# CurrentMeter.net
KiCad netlist of a schematic drawn in Altium Designer
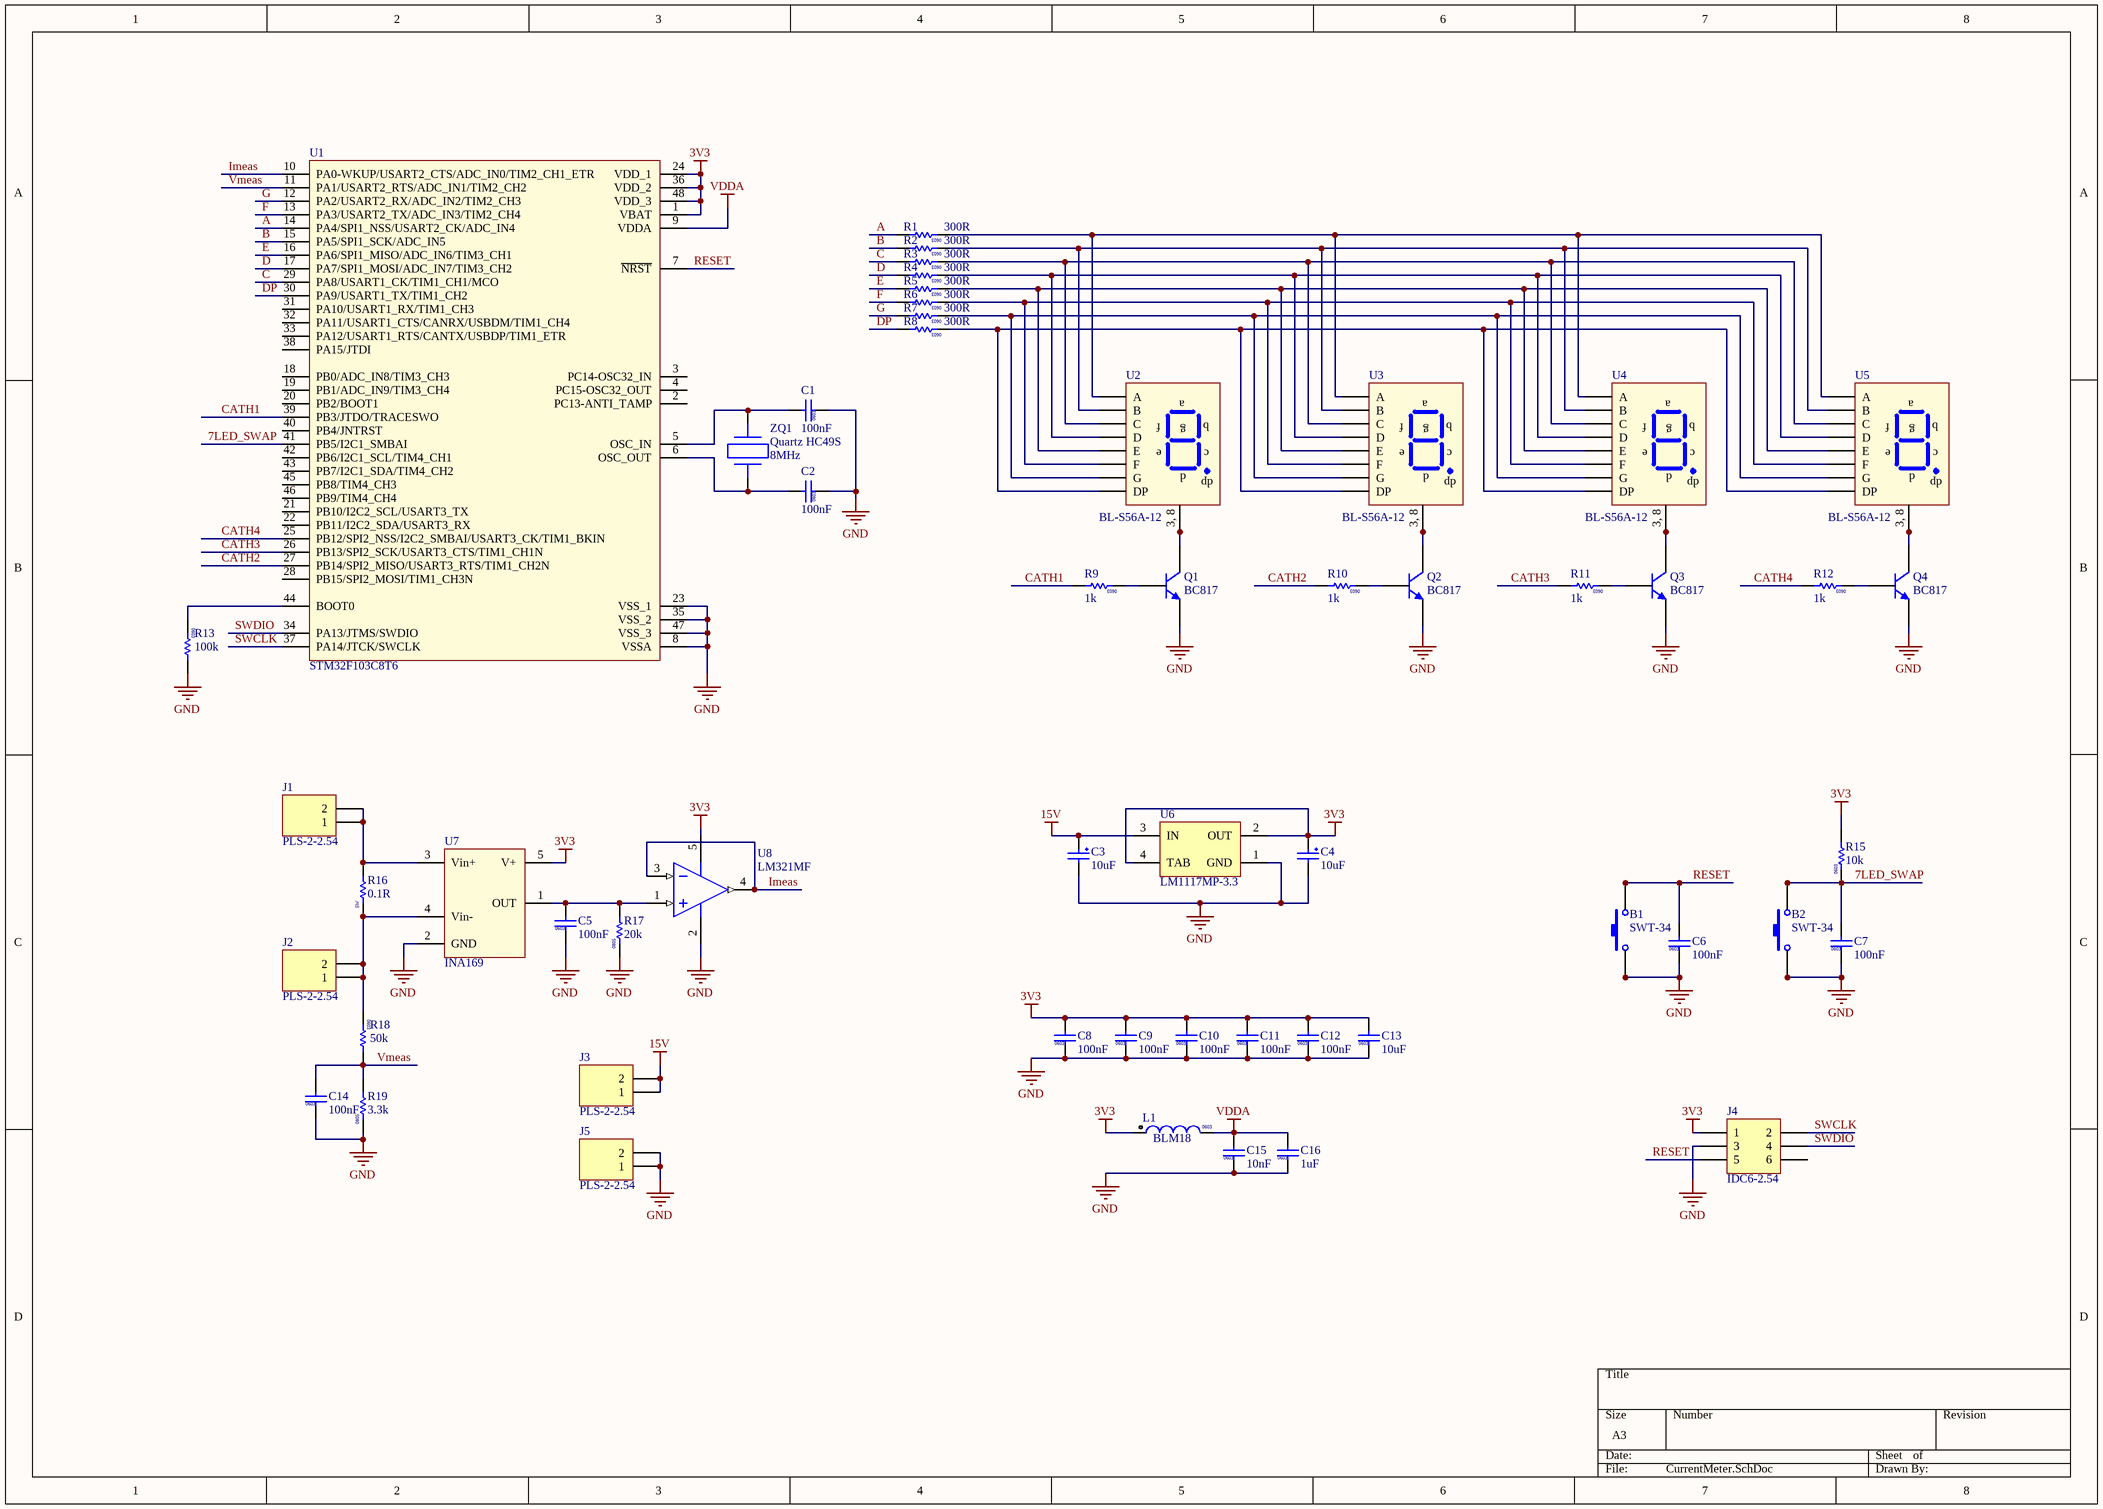
[diagram p0: CurrentMeter.SchDoc]

(export (version "E")
  (design (tool "Eeschema 10.0.6"))
  (components
    (comp (ref "B1")
      (value "SWT-34")
      (footprint "SWT-34")
      (description "KLS7-TS6604-7.0-180-T, SMD Button h=7mm")
      (libsource (lib "Connectors_dif") (part "SWT-34"))
    )
    (comp (ref "B2")
      (value "SWT-34")
      (footprint "SWT-34")
      (description "KLS7-TS6604-7.0-180-T, SMD Button h=7mm")
      (libsource (lib "Connectors_dif") (part "SWT-34"))
    )
    (comp (ref "C1")
      (value "100nF")
      (footprint "CAPC1608-0603N")
      (description "Capacitor 0603")
      (fields (field (name "Comment") "CAPC_0603"))
      (libsource (lib "Passive") (part "CAPC_0603"))
    )
    (comp (ref "C2")
      (value "100nF")
      (footprint "CAPC1608-0603N")
      (description "Capacitor 0603")
      (fields (field (name "Comment") "CAPC_0603"))
      (libsource (lib "Passive") (part "CAPC_0603"))
    )
    (comp (ref "C3")
      (value "10uF")
      (footprint "TCAPC_A")
      (description "Capacitor tantalum SMD type A")
      (fields (field (name "Comment") "TCAPC_A"))
      (libsource (lib "Passive") (part "TCAPC_A"))
    )
    (comp (ref "C4")
      (value "10uF")
      (footprint "TCAPC_A")
      (description "Capacitor tantalum SMD type A")
      (fields (field (name "Comment") "TCAPC_A"))
      (libsource (lib "Passive") (part "TCAPC_A"))
    )
    (comp (ref "C5")
      (value "100nF")
      (footprint "CAPC1608-0603N")
      (description "Capacitor 0603")
      (fields (field (name "Comment") "CAPC_0603"))
      (libsource (lib "Passive") (part "CAPC_0603"))
    )
    (comp (ref "C6")
      (value "100nF")
      (footprint "CAPC1608-0603N")
      (description "Capacitor 0603")
      (fields (field (name "Comment") "CAPC_0603"))
      (libsource (lib "Passive") (part "CAPC_0603"))
    )
    (comp (ref "C7")
      (value "100nF")
      (footprint "CAPC1608-0603N")
      (description "Capacitor 0603")
      (fields (field (name "Comment") "CAPC_0603"))
      (libsource (lib "Passive") (part "CAPC_0603"))
    )
    (comp (ref "C8")
      (value "100nF")
      (footprint "CAPC1608-0603N")
      (description "Capacitor 0603")
      (fields (field (name "Comment") "CAPC_0603"))
      (libsource (lib "Passive") (part "CAPC_0603"))
    )
    (comp (ref "C9")
      (value "100nF")
      (footprint "CAPC1608-0603N")
      (description "Capacitor 0603")
      (fields (field (name "Comment") "CAPC_0603"))
      (libsource (lib "Passive") (part "CAPC_0603"))
    )
    (comp (ref "C10")
      (value "100nF")
      (footprint "CAPC1608-0603N")
      (description "Capacitor 0603")
      (fields (field (name "Comment") "CAPC_0603"))
      (libsource (lib "Passive") (part "CAPC_0603"))
    )
    (comp (ref "C11")
      (value "100nF")
      (footprint "CAPC1608-0603N")
      (description "Capacitor 0603")
      (fields (field (name "Comment") "CAPC_0603"))
      (libsource (lib "Passive") (part "CAPC_0603"))
    )
    (comp (ref "C12")
      (value "100nF")
      (footprint "CAPC1608-0603N")
      (description "Capacitor 0603")
      (fields (field (name "Comment") "CAPC_0603"))
      (libsource (lib "Passive") (part "CAPC_0603"))
    )
    (comp (ref "C13")
      (value "10uF")
      (footprint "CAPC1608-0603N")
      (description "Capacitor 0603")
      (fields (field (name "Comment") "CAPC_0603"))
      (libsource (lib "Passive") (part "CAPC_0603"))
    )
    (comp (ref "C14")
      (value "100nF")
      (footprint "CAPC1608-0603N")
      (description "Capacitor 0603")
      (fields (field (name "Comment") "CAPC_0603"))
      (libsource (lib "Passive") (part "CAPC_0603"))
    )
    (comp (ref "C15")
      (value "10nF")
      (footprint "CAPC1608-0603N")
      (description "Capacitor 0603")
      (fields (field (name "Comment") "CAPC_0603"))
      (libsource (lib "Passive") (part "CAPC_0603"))
    )
    (comp (ref "C16")
      (value "1uF")
      (footprint "CAPC1608-0603N")
      (description "Capacitor 0603")
      (fields (field (name "Comment") "CAPC_0603"))
      (libsource (lib "Passive") (part "CAPC_0603"))
    )
    (comp (ref "J1")
      (value "PLS-2-2.54")
      (footprint "PLS-2-2.54")
      (fields (field (name "PUBLISHER") "Altium Limited"))
      (libsource (lib "Connectors_dif") (part "PLS-2-2.54"))
    )
    (comp (ref "J2")
      (value "PLS-2-2.54")
      (footprint "PLS-2-2.54")
      (fields (field (name "PUBLISHER") "Altium Limited"))
      (libsource (lib "Connectors_dif") (part "PLS-2-2.54"))
    )
    (comp (ref "J3")
      (value "PLS-2-2.54")
      (footprint "PLS-2-2.54")
      (fields (field (name "PUBLISHER") "Altium Limited"))
      (libsource (lib "Connectors_dif") (part "PLS-2-2.54"))
    )
    (comp (ref "J4")
      (value "IDC6-2.54")
      (footprint "IDC6-2.54")
      (description "IDC6 2.54 mm pitch Straight, plastic Box")
      (libsource (lib "Connectors_dif") (part "IDC6-2.54"))
    )
    (comp (ref "J5")
      (value "PLS-2-2.54")
      (footprint "PLS-2-2.54")
      (fields (field (name "PUBLISHER") "Altium Limited"))
      (libsource (lib "Connectors_dif") (part "PLS-2-2.54"))
    )
    (comp (ref "L1")
      (value "BLM18")
      (footprint "INDC1608AN")
      (description "Chip Inductor, Body Body 1.6x0.8mm")
      (fields (field (name "Comment") "INDC-0603"))
      (libsource (lib "Passive") (part "INDC-0603"))
    )
    (comp (ref "Q1")
      (value "BC817")
      (footprint "SOT23-3N")
      (description "BC817 NPN Transistor")
      (libsource (lib "Discrete") (part "BC817"))
    )
    (comp (ref "Q2")
      (value "BC817")
      (footprint "SOT23-3N")
      (description "BC817 NPN Transistor")
      (libsource (lib "Discrete") (part "BC817"))
    )
    (comp (ref "Q3")
      (value "BC817")
      (footprint "SOT23-3N")
      (description "BC817 NPN Transistor")
      (libsource (lib "Discrete") (part "BC817"))
    )
    (comp (ref "Q4")
      (value "BC817")
      (footprint "SOT23-3N")
      (description "BC817 NPN Transistor")
      (libsource (lib "Discrete") (part "BC817"))
    )
    (comp (ref "R1")
      (value "300R")
      (footprint "RESC1608-0603N")
      (description "Resistor 0603")
      (fields (field (name "Comment") "RESC_0603"))
      (libsource (lib "Passive") (part "RESC_0603"))
    )
    (comp (ref "R2")
      (value "300R")
      (footprint "RESC1608-0603N")
      (description "Resistor 0603")
      (fields (field (name "Comment") "RESC_0603"))
      (libsource (lib "Passive") (part "RESC_0603"))
    )
    (comp (ref "R3")
      (value "300R")
      (footprint "RESC1608-0603N")
      (description "Resistor 0603")
      (fields (field (name "Comment") "RESC_0603"))
      (libsource (lib "Passive") (part "RESC_0603"))
    )
    (comp (ref "R4")
      (value "300R")
      (footprint "RESC1608-0603N")
      (description "Resistor 0603")
      (fields (field (name "Comment") "RESC_0603"))
      (libsource (lib "Passive") (part "RESC_0603"))
    )
    (comp (ref "R5")
      (value "300R")
      (footprint "RESC1608-0603N")
      (description "Resistor 0603")
      (fields (field (name "Comment") "RESC_0603"))
      (libsource (lib "Passive") (part "RESC_0603"))
    )
    (comp (ref "R6")
      (value "300R")
      (footprint "RESC1608-0603N")
      (description "Resistor 0603")
      (fields (field (name "Comment") "RESC_0603"))
      (libsource (lib "Passive") (part "RESC_0603"))
    )
    (comp (ref "R7")
      (value "300R")
      (footprint "RESC1608-0603N")
      (description "Resistor 0603")
      (fields (field (name "Comment") "RESC_0603"))
      (libsource (lib "Passive") (part "RESC_0603"))
    )
    (comp (ref "R8")
      (value "300R")
      (footprint "RESC1608-0603N")
      (description "Resistor 0603")
      (fields (field (name "Comment") "RESC_0603"))
      (libsource (lib "Passive") (part "RESC_0603"))
    )
    (comp (ref "R9")
      (value "1k")
      (footprint "RESC1608-0603N")
      (description "Resistor 0603")
      (fields (field (name "Comment") "RESC_0603"))
      (libsource (lib "Passive") (part "RESC_0603"))
    )
    (comp (ref "R10")
      (value "1k")
      (footprint "RESC1608-0603N")
      (description "Resistor 0603")
      (fields (field (name "Comment") "RESC_0603"))
      (libsource (lib "Passive") (part "RESC_0603"))
    )
    (comp (ref "R11")
      (value "1k")
      (footprint "RESC1608-0603N")
      (description "Resistor 0603")
      (fields (field (name "Comment") "RESC_0603"))
      (libsource (lib "Passive") (part "RESC_0603"))
    )
    (comp (ref "R12")
      (value "1k")
      (footprint "RESC1608-0603N")
      (description "Resistor 0603")
      (fields (field (name "Comment") "RESC_0603"))
      (libsource (lib "Passive") (part "RESC_0603"))
    )
    (comp (ref "R13")
      (value "100k")
      (footprint "RESC1608-0603M")
      (description "Resistor 0603")
      (fields (field (name "Comment") "RESC_0603"))
      (libsource (lib "Passive") (part "RESC_0603"))
    )
    (comp (ref "R15")
      (value "10k")
      (footprint "RESC1608-0603N")
      (description "Resistor 0603")
      (fields (field (name "Comment") "RESC_0603"))
      (libsource (lib "Passive") (part "RESC_0603"))
    )
    (comp (ref "R16")
      (value "0.1R")
      (footprint "RES5W")
      (description "Resistor 5W")
      (fields (field (name "Comment") "RES_5W"))
      (libsource (lib "Passive") (part "RES_5W"))
    )
    (comp (ref "R17")
      (value "20k")
      (footprint "RESC2012-0805N")
      (description "Resistor 0805")
      (fields (field (name "Comment") "RESC_0805"))
      (libsource (lib "Passive") (part "RESC_0805"))
    )
    (comp (ref "R18")
      (value "50k")
      (footprint "RESC1608-0603N")
      (description "Resistor 0603")
      (fields (field (name "Comment") "RESC_0603"))
      (libsource (lib "Passive") (part "RESC_0603"))
    )
    (comp (ref "R19")
      (value "3.3k")
      (footprint "RESC2012-0805N")
      (description "Resistor 0805")
      (fields (field (name "Comment") "RESC_0805"))
      (libsource (lib "Passive") (part "RESC_0805"))
    )
    (comp (ref "U1")
      (value "STM32F103C8T6")
      (footprint "QFP48_L")
      (libsource (lib "Digital_IC") (part "STM32F103C8T6"))
    )
    (comp (ref "U2")
      (value "BL-S56A-12")
      (footprint "BL-S56A-12")
      (description "LED Numeric Display, 1 Digit")
      (libsource (lib "Discrete") (part "BL-S56A-12"))
    )
    (comp (ref "U3")
      (value "BL-S56A-12")
      (footprint "BL-S56A-12")
      (description "LED Numeric Display, 1 Digit")
      (libsource (lib "Discrete") (part "BL-S56A-12"))
    )
    (comp (ref "U4")
      (value "BL-S56A-12")
      (footprint "BL-S56A-12")
      (description "LED Numeric Display, 1 Digit")
      (libsource (lib "Discrete") (part "BL-S56A-12"))
    )
    (comp (ref "U5")
      (value "BL-S56A-12")
      (footprint "BL-S56A-12")
      (description "LED Numeric Display, 1 Digit")
      (libsource (lib "Discrete") (part "BL-S56A-12"))
    )
    (comp (ref "U6")
      (value "LM1117MP-3.3")
      (footprint "MP04A_N")
      (description "800mA Low-Dropout Linear Regulator")
      (fields
        (field (name "MANUFACTURER") "National Semiconductor")
        (field (name "DIGIKEYPARTNUMBER") "LM1117MP-3.3CT-ND")
        (field (name "PUBLISHER") "Altium Limited")
      )
      (libsource (lib "Analog_IC") (part "LM1117MP-3.3"))
    )
    (comp (ref "U7")
      (value "INA169")
      (footprint "INA169_N")
      (description "High-side Current Shunt Monitor")
      (libsource (lib "Analog_IC") (part "INA169"))
    )
    (comp (ref "U8")
      (value "LM321MF")
      (footprint "MF05A_N")
      (description "Low Power Single Op Amp")
      (fields
        (field (name "MANUFACTURER") "National Semiconductor")
        (field (name "DIGIKEYPARTNUMBER") "LM321MFCT-ND")
        (field (name "PUBLISHER") "Altium Limited")
      )
      (libsource (lib "Analog_IC") (part "LM321MF"))
    )
    (comp (ref "ZQ1")
      (value "Quartz HC49S")
      (footprint "HC-49S")
      (fields (field (name "ALTIUM_VALUE") "8MHz"))
      (libsource (lib "Passive") (part "Quartz HC49S"))
    )
  )
  (nets
    (net (code "1") (name "/7LED_SWAP") (class "Default")
      (node (ref "B2") (pin "3") (pinfunction "3_3") (pintype "passive"))
      (node (ref "B2") (pin "4") (pinfunction "4_4") (pintype "passive"))
      (node (ref "C7") (pin "2") (pinfunction "2_2") (pintype "passive"))
      (node (ref "R15") (pin "1") (pinfunction "1_1") (pintype "passive"))
      (node (ref "U1") (pin "41") (pinfunction "PB5/I2C1_SMBAI_41") (pintype "passive"))
    )
    (net (code "2") (name "/A") (class "Default")
      (node (ref "R1") (pin "2") (pinfunction "2_2") (pintype "passive"))
      (node (ref "U1") (pin "14") (pinfunction "PA4/SPI1_NSS/USART2_CK/ADC_IN4_14") (pintype "passive"))
    )
    (net (code "3") (name "/B") (class "Default")
      (node (ref "R2") (pin "2") (pinfunction "2_2") (pintype "passive"))
      (node (ref "U1") (pin "15") (pinfunction "PA5/SPI1_SCK/ADC_IN5_15") (pintype "passive"))
    )
    (net (code "4") (name "/C") (class "Default")
      (node (ref "R3") (pin "2") (pinfunction "2_2") (pintype "passive"))
      (node (ref "U1") (pin "29") (pinfunction "PA8/USART1_CK/TIM1_CH1/MCO_29") (pintype "passive"))
    )
    (net (code "5") (name "/CATH1") (class "Default")
      (node (ref "R9") (pin "2") (pinfunction "2_2") (pintype "passive"))
      (node (ref "U1") (pin "39") (pinfunction "PB3/JTDO/TRACESWO_39") (pintype "passive"))
    )
    (net (code "6") (name "/CATH2") (class "Default")
      (node (ref "R10") (pin "2") (pinfunction "2_2") (pintype "passive"))
      (node (ref "U1") (pin "27") (pinfunction "PB14/SPI2_MISO/USART3_RTS/TIM1_CH2N_27") (pintype "passive"))
    )
    (net (code "7") (name "/CATH3") (class "Default")
      (node (ref "R11") (pin "2") (pinfunction "2_2") (pintype "passive"))
      (node (ref "U1") (pin "26") (pinfunction "PB13/SPI2_SCK/USART3_CTS/TIM1_CH1N_26") (pintype "passive"))
    )
    (net (code "8") (name "/CATH4") (class "Default")
      (node (ref "R12") (pin "2") (pinfunction "2_2") (pintype "passive"))
      (node (ref "U1") (pin "25") (pinfunction "PB12/SPI2_NSS/I2C2_SMBAI/USART3_CK/TIM1_BKIN_25") (pintype "passive"))
    )
    (net (code "9") (name "/D") (class "Default")
      (node (ref "R4") (pin "2") (pinfunction "2_2") (pintype "passive"))
      (node (ref "U1") (pin "17") (pinfunction "PA7/SPI1_MOSI/ADC_IN7/TIM3_CH2_17") (pintype "passive"))
    )
    (net (code "10") (name "/DP") (class "Default")
      (node (ref "R8") (pin "2") (pinfunction "2_2") (pintype "passive"))
      (node (ref "U1") (pin "30") (pinfunction "PA9/USART1_TX/TIM1_CH2_30") (pintype "passive"))
    )
    (net (code "11") (name "/E") (class "Default")
      (node (ref "R5") (pin "2") (pinfunction "2_2") (pintype "passive"))
      (node (ref "U1") (pin "16") (pinfunction "PA6/SPI1_MISO/ADC_IN6/TIM3_CH1_16") (pintype "passive"))
    )
    (net (code "12") (name "/F") (class "Default")
      (node (ref "R6") (pin "2") (pinfunction "2_2") (pintype "passive"))
      (node (ref "U1") (pin "13") (pinfunction "PA3/USART2_TX/ADC_IN3/TIM2_CH4_13") (pintype "passive"))
    )
    (net (code "13") (name "/G") (class "Default")
      (node (ref "R7") (pin "2") (pinfunction "2_2") (pintype "passive"))
      (node (ref "U1") (pin "12") (pinfunction "PA2/USART2_RX/ADC_IN2/TIM2_CH3_12") (pintype "passive"))
    )
    (net (code "14") (name "/Imeas") (class "Default")
      (node (ref "U1") (pin "10") (pinfunction "PA0-WKUP/USART2_CTS/ADC_IN0/TIM2_CH1_ETR_10") (pintype "passive"))
      (node (ref "U8") (pin "3") (pinfunction "IN-_3") (pintype "input"))
      (node (ref "U8") (pin "4") (pinfunction "OUT_4") (pintype "output"))
    )
    (net (code "15") (name "/RESET") (class "Default")
      (node (ref "B1") (pin "3") (pinfunction "3_3") (pintype "passive"))
      (node (ref "B1") (pin "4") (pinfunction "4_4") (pintype "passive"))
      (node (ref "C6") (pin "2") (pinfunction "2_2") (pintype "passive"))
      (node (ref "J4") (pin "5") (pinfunction "5_5") (pintype "passive"))
      (node (ref "U1") (pin "7") (pinfunction "~{NRST}_7") (pintype "passive"))
    )
    (net (code "16") (name "/SWCLK") (class "Default")
      (node (ref "J4") (pin "2") (pinfunction "2_2") (pintype "passive"))
      (node (ref "U1") (pin "37") (pinfunction "PA14/JTCK/SWCLK_37") (pintype "passive"))
    )
    (net (code "17") (name "/SWDIO") (class "Default")
      (node (ref "J4") (pin "4") (pinfunction "4_4") (pintype "passive"))
      (node (ref "U1") (pin "34") (pinfunction "PA13/JTMS/SWDIO_34") (pintype "passive"))
    )
    (net (code "18") (name "/Vmeas") (class "Default")
      (node (ref "C14") (pin "2") (pinfunction "2_2") (pintype "passive"))
      (node (ref "R18") (pin "2") (pinfunction "2_2") (pintype "passive"))
      (node (ref "R19") (pin "2") (pinfunction "2_2") (pintype "passive"))
      (node (ref "U1") (pin "11") (pinfunction "PA1/USART2_RTS/ADC_IN1/TIM2_CH2_11") (pintype "passive"))
    )
    (net (code "19") (name "3V3") (class "Default")
      (node (ref "C10") (pin "2") (pinfunction "2_2") (pintype "passive"))
      (node (ref "C11") (pin "2") (pinfunction "2_2") (pintype "passive"))
      (node (ref "C12") (pin "2") (pinfunction "2_2") (pintype "passive"))
      (node (ref "C13") (pin "2") (pinfunction "2_2") (pintype "passive"))
      (node (ref "C4") (pin "1") (pinfunction "1_1") (pintype "passive"))
      (node (ref "C8") (pin "2") (pinfunction "2_2") (pintype "passive"))
      (node (ref "C9") (pin "2") (pinfunction "2_2") (pintype "passive"))
      (node (ref "J4") (pin "1") (pinfunction "1_1") (pintype "passive"))
      (node (ref "L1") (pin "1") (pinfunction "1_1") (pintype "passive"))
      (node (ref "R15") (pin "2") (pinfunction "2_2") (pintype "passive"))
      (node (ref "U1") (pin "1") (pinfunction "VBAT_1") (pintype "passive"))
      (node (ref "U1") (pin "24") (pinfunction "VDD_1_24") (pintype "passive"))
      (node (ref "U1") (pin "36") (pinfunction "VDD_2_36") (pintype "passive"))
      (node (ref "U1") (pin "48") (pinfunction "VDD_3_48") (pintype "passive"))
      (node (ref "U6") (pin "2") (pinfunction "OUT_2") (pintype "power_in"))
      (node (ref "U6") (pin "4") (pinfunction "TAB_4") (pintype "power_in"))
      (node (ref "U7") (pin "5") (pinfunction "V+_5") (pintype "passive"))
      (node (ref "U8") (pin "5") (pinfunction "V+_5") (pintype "power_in"))
    )
    (net (code "20") (name "15V") (class "Default")
      (node (ref "C3") (pin "1") (pinfunction "1_1") (pintype "passive"))
      (node (ref "J3") (pin "1") (pinfunction "1_1") (pintype "passive"))
      (node (ref "J3") (pin "2") (pinfunction "2_2") (pintype "passive"))
      (node (ref "U6") (pin "3") (pinfunction "IN_3") (pintype "power_in"))
    )
    (net (code "21") (name "GND") (class "Default")
      (node (ref "B1") (pin "1") (pinfunction "1_1") (pintype "passive"))
      (node (ref "B1") (pin "2") (pinfunction "2_2") (pintype "passive"))
      (node (ref "B2") (pin "1") (pinfunction "1_1") (pintype "passive"))
      (node (ref "B2") (pin "2") (pinfunction "2_2") (pintype "passive"))
      (node (ref "C1") (pin "1") (pinfunction "1_1") (pintype "passive"))
      (node (ref "C10") (pin "1") (pinfunction "1_1") (pintype "passive"))
      (node (ref "C11") (pin "1") (pinfunction "1_1") (pintype "passive"))
      (node (ref "C12") (pin "1") (pinfunction "1_1") (pintype "passive"))
      (node (ref "C13") (pin "1") (pinfunction "1_1") (pintype "passive"))
      (node (ref "C14") (pin "1") (pinfunction "1_1") (pintype "passive"))
      (node (ref "C15") (pin "1") (pinfunction "1_1") (pintype "passive"))
      (node (ref "C16") (pin "1") (pinfunction "1_1") (pintype "passive"))
      (node (ref "C2") (pin "1") (pinfunction "1_1") (pintype "passive"))
      (node (ref "C3") (pin "2") (pinfunction "2_2") (pintype "passive"))
      (node (ref "C4") (pin "2") (pinfunction "2_2") (pintype "passive"))
      (node (ref "C5") (pin "1") (pinfunction "1_1") (pintype "passive"))
      (node (ref "C6") (pin "1") (pinfunction "1_1") (pintype "passive"))
      (node (ref "C7") (pin "1") (pinfunction "1_1") (pintype "passive"))
      (node (ref "C8") (pin "1") (pinfunction "1_1") (pintype "passive"))
      (node (ref "C9") (pin "1") (pinfunction "1_1") (pintype "passive"))
      (node (ref "J4") (pin "3") (pinfunction "3_3") (pintype "passive"))
      (node (ref "J5") (pin "1") (pinfunction "1_1") (pintype "passive"))
      (node (ref "J5") (pin "2") (pinfunction "2_2") (pintype "passive"))
      (node (ref "Q1") (pin "2") (pinfunction "E_2") (pintype "passive"))
      (node (ref "Q2") (pin "2") (pinfunction "E_2") (pintype "passive"))
      (node (ref "Q3") (pin "2") (pinfunction "E_2") (pintype "passive"))
      (node (ref "Q4") (pin "2") (pinfunction "E_2") (pintype "passive"))
      (node (ref "R13") (pin "2") (pinfunction "2_2") (pintype "passive"))
      (node (ref "R17") (pin "1") (pinfunction "1_1") (pintype "passive"))
      (node (ref "R19") (pin "1") (pinfunction "1_1") (pintype "passive"))
      (node (ref "U1") (pin "23") (pinfunction "VSS_1_23") (pintype "passive"))
      (node (ref "U1") (pin "35") (pinfunction "VSS_2_35") (pintype "passive"))
      (node (ref "U1") (pin "47") (pinfunction "VSS_3_47") (pintype "passive"))
      (node (ref "U1") (pin "8") (pinfunction "VSSA_8") (pintype "passive"))
      (node (ref "U6") (pin "1") (pinfunction "GND_1") (pintype "power_in"))
      (node (ref "U7") (pin "2") (pinfunction "GND_2") (pintype "passive"))
      (node (ref "U8") (pin "2") (pinfunction "V-_2") (pintype "power_in"))
    )
    (net (code "22") (name "Net-(Q1-B)") (class "Default")
      (node (ref "Q1") (pin "1") (pinfunction "B_1") (pintype "passive"))
      (node (ref "R9") (pin "1") (pinfunction "1_1") (pintype "passive"))
    )
    (net (code "23") (name "Net-(Q1-C)") (class "Default")
      (node (ref "Q1") (pin "3") (pinfunction "C_3") (pintype "passive"))
      (node (ref "U2") (pin "3") (pinfunction "CATHODE_3") (pintype "passive"))
      (node (ref "U2") (pin "8") (pinfunction "CATHODE_8") (pintype "passive"))
    )
    (net (code "24") (name "Net-(Q2-B)") (class "Default")
      (node (ref "Q2") (pin "1") (pinfunction "B_1") (pintype "passive"))
      (node (ref "R10") (pin "1") (pinfunction "1_1") (pintype "passive"))
    )
    (net (code "25") (name "Net-(Q2-C)") (class "Default")
      (node (ref "Q2") (pin "3") (pinfunction "C_3") (pintype "passive"))
      (node (ref "U3") (pin "3") (pinfunction "CATHODE_3") (pintype "passive"))
      (node (ref "U3") (pin "8") (pinfunction "CATHODE_8") (pintype "passive"))
    )
    (net (code "26") (name "Net-(Q3-B)") (class "Default")
      (node (ref "Q3") (pin "1") (pinfunction "B_1") (pintype "passive"))
      (node (ref "R11") (pin "1") (pinfunction "1_1") (pintype "passive"))
    )
    (net (code "27") (name "Net-(Q3-C)") (class "Default")
      (node (ref "Q3") (pin "3") (pinfunction "C_3") (pintype "passive"))
      (node (ref "U4") (pin "3") (pinfunction "CATHODE_3") (pintype "passive"))
      (node (ref "U4") (pin "8") (pinfunction "CATHODE_8") (pintype "passive"))
    )
    (net (code "28") (name "Net-(Q4-B)") (class "Default")
      (node (ref "Q4") (pin "1") (pinfunction "B_1") (pintype "passive"))
      (node (ref "R12") (pin "1") (pinfunction "1_1") (pintype "passive"))
    )
    (net (code "29") (name "Net-(Q4-C)") (class "Default")
      (node (ref "Q4") (pin "3") (pinfunction "C_3") (pintype "passive"))
      (node (ref "U5") (pin "3") (pinfunction "CATHODE_3") (pintype "passive"))
      (node (ref "U5") (pin "8") (pinfunction "CATHODE_8") (pintype "passive"))
    )
    (net (code "30") (name "Net-(U1-BOOT0)") (class "Default")
      (node (ref "R13") (pin "1") (pinfunction "1_1") (pintype "passive"))
      (node (ref "U1") (pin "44") (pinfunction "BOOT0_44") (pintype "passive"))
    )
    (net (code "31") (name "Net-(U1-OSC_IN)") (class "Default")
      (node (ref "C1") (pin "2") (pinfunction "2_2") (pintype "passive"))
      (node (ref "U1") (pin "5") (pinfunction "OSC_IN_5") (pintype "passive"))
      (node (ref "ZQ1") (pin "2") (pinfunction "2_2") (pintype "passive"))
    )
    (net (code "32") (name "Net-(U1-OSC_OUT)") (class "Default")
      (node (ref "C2") (pin "2") (pinfunction "2_2") (pintype "passive"))
      (node (ref "U1") (pin "6") (pinfunction "OSC_OUT_6") (pintype "passive"))
      (node (ref "ZQ1") (pin "1") (pinfunction "1_1") (pintype "passive"))
    )
    (net (code "33") (name "Net-(U2-A)") (class "Default")
      (node (ref "R1") (pin "1") (pinfunction "1_1") (pintype "passive"))
      (node (ref "U2") (pin "7") (pinfunction "A_7") (pintype "passive"))
      (node (ref "U3") (pin "7") (pinfunction "A_7") (pintype "passive"))
      (node (ref "U4") (pin "7") (pinfunction "A_7") (pintype "passive"))
      (node (ref "U5") (pin "7") (pinfunction "A_7") (pintype "passive"))
    )
    (net (code "34") (name "Net-(U2-B)") (class "Default")
      (node (ref "R2") (pin "1") (pinfunction "1_1") (pintype "passive"))
      (node (ref "U2") (pin "6") (pinfunction "B_6") (pintype "passive"))
      (node (ref "U3") (pin "6") (pinfunction "B_6") (pintype "passive"))
      (node (ref "U4") (pin "6") (pinfunction "B_6") (pintype "passive"))
      (node (ref "U5") (pin "6") (pinfunction "B_6") (pintype "passive"))
    )
    (net (code "35") (name "Net-(U2-C)") (class "Default")
      (node (ref "R3") (pin "1") (pinfunction "1_1") (pintype "passive"))
      (node (ref "U2") (pin "4") (pinfunction "C_4") (pintype "passive"))
      (node (ref "U3") (pin "4") (pinfunction "C_4") (pintype "passive"))
      (node (ref "U4") (pin "4") (pinfunction "C_4") (pintype "passive"))
      (node (ref "U5") (pin "4") (pinfunction "C_4") (pintype "passive"))
    )
    (net (code "36") (name "Net-(U2-D)") (class "Default")
      (node (ref "R4") (pin "1") (pinfunction "1_1") (pintype "passive"))
      (node (ref "U2") (pin "2") (pinfunction "D_2") (pintype "passive"))
      (node (ref "U3") (pin "2") (pinfunction "D_2") (pintype "passive"))
      (node (ref "U4") (pin "2") (pinfunction "D_2") (pintype "passive"))
      (node (ref "U5") (pin "2") (pinfunction "D_2") (pintype "passive"))
    )
    (net (code "37") (name "Net-(U2-DP)") (class "Default")
      (node (ref "R8") (pin "1") (pinfunction "1_1") (pintype "passive"))
      (node (ref "U2") (pin "5") (pinfunction "DP_5") (pintype "passive"))
      (node (ref "U3") (pin "5") (pinfunction "DP_5") (pintype "passive"))
      (node (ref "U4") (pin "5") (pinfunction "DP_5") (pintype "passive"))
      (node (ref "U5") (pin "5") (pinfunction "DP_5") (pintype "passive"))
    )
    (net (code "38") (name "Net-(U2-E)") (class "Default")
      (node (ref "R5") (pin "1") (pinfunction "1_1") (pintype "passive"))
      (node (ref "U2") (pin "1") (pinfunction "E_1") (pintype "passive"))
      (node (ref "U3") (pin "1") (pinfunction "E_1") (pintype "passive"))
      (node (ref "U4") (pin "1") (pinfunction "E_1") (pintype "passive"))
      (node (ref "U5") (pin "1") (pinfunction "E_1") (pintype "passive"))
    )
    (net (code "39") (name "Net-(U2-F)") (class "Default")
      (node (ref "R6") (pin "1") (pinfunction "1_1") (pintype "passive"))
      (node (ref "U2") (pin "9") (pinfunction "F_9") (pintype "passive"))
      (node (ref "U3") (pin "9") (pinfunction "F_9") (pintype "passive"))
      (node (ref "U4") (pin "9") (pinfunction "F_9") (pintype "passive"))
      (node (ref "U5") (pin "9") (pinfunction "F_9") (pintype "passive"))
    )
    (net (code "40") (name "Net-(U2-G)") (class "Default")
      (node (ref "R7") (pin "1") (pinfunction "1_1") (pintype "passive"))
      (node (ref "U2") (pin "10") (pinfunction "G_10") (pintype "passive"))
      (node (ref "U3") (pin "10") (pinfunction "G_10") (pintype "passive"))
      (node (ref "U4") (pin "10") (pinfunction "G_10") (pintype "passive"))
      (node (ref "U5") (pin "10") (pinfunction "G_10") (pintype "passive"))
    )
    (net (code "41") (name "Net-(U7-OUT)") (class "Default")
      (node (ref "C5") (pin "2") (pinfunction "2_2") (pintype "passive"))
      (node (ref "R17") (pin "2") (pinfunction "2_2") (pintype "passive"))
      (node (ref "U7") (pin "1") (pinfunction "OUT_1") (pintype "passive"))
      (node (ref "U8") (pin "1") (pinfunction "IN+_1") (pintype "input"))
    )
    (net (code "42") (name "Net-(U7-Vin+)") (class "Default")
      (node (ref "J1") (pin "1") (pinfunction "1_1") (pintype "passive"))
      (node (ref "J1") (pin "2") (pinfunction "2_2") (pintype "passive"))
      (node (ref "R16") (pin "2") (pinfunction "2_2") (pintype "passive"))
      (node (ref "U7") (pin "3") (pinfunction "Vin+_3") (pintype "passive"))
    )
    (net (code "43") (name "Net-(U7-Vin-)") (class "Default")
      (node (ref "J2") (pin "1") (pinfunction "1_1") (pintype "passive"))
      (node (ref "J2") (pin "2") (pinfunction "2_2") (pintype "passive"))
      (node (ref "R16") (pin "1") (pinfunction "1_1") (pintype "passive"))
      (node (ref "R18") (pin "1") (pinfunction "1_1") (pintype "passive"))
      (node (ref "U7") (pin "4") (pinfunction "Vin-_4") (pintype "passive"))
    )
    (net (code "44") (name "VDDA") (class "Default")
      (node (ref "C15") (pin "2") (pinfunction "2_2") (pintype "passive"))
      (node (ref "C16") (pin "2") (pinfunction "2_2") (pintype "passive"))
      (node (ref "L1") (pin "2") (pinfunction "2_2") (pintype "passive"))
      (node (ref "U1") (pin "9") (pinfunction "VDDA_9") (pintype "passive"))
    )
    (net (code "45") (name "unconnected-(J4-Pad6)") (class "Default")
      (node (ref "J4") (pin "6") (pinfunction "6_6") (pintype "passive"))
    )
    (net (code "46") (name "unconnected-(U1-PA10{slash}USART1_RX{slash}TIM1_CH3-Pad31)") (class "Default")
      (node (ref "U1") (pin "31") (pinfunction "PA10/USART1_RX/TIM1_CH3_31") (pintype "passive"))
    )
    (net (code "47") (name "unconnected-(U1-PA11{slash}USART1_CTS{slash}CANRX{slash}USBDM{slash}TIM1_CH4-Pad32)") (class "Default")
      (node (ref "U1") (pin "32") (pinfunction "PA11/USART1_CTS/CANRX/USBDM/TIM1_CH4_32") (pintype "passive"))
    )
    (net (code "48") (name "unconnected-(U1-PA12{slash}USART1_RTS{slash}CANTX{slash}USBDP{slash}TIM1_ETR-Pad33)") (class "Default")
      (node (ref "U1") (pin "33") (pinfunction "PA12/USART1_RTS/CANTX/USBDP/TIM1_ETR_33") (pintype "passive"))
    )
    (net (code "49") (name "unconnected-(U1-PA15{slash}JTDI-Pad38)") (class "Default")
      (node (ref "U1") (pin "38") (pinfunction "PA15/JTDI_38") (pintype "passive"))
    )
    (net (code "50") (name "unconnected-(U1-PB0{slash}ADC_IN8{slash}TIM3_CH3-Pad18)") (class "Default")
      (node (ref "U1") (pin "18") (pinfunction "PB0/ADC_IN8/TIM3_CH3_18") (pintype "passive"))
    )
    (net (code "51") (name "unconnected-(U1-PB1{slash}ADC_IN9{slash}TIM3_CH4-Pad19)") (class "Default")
      (node (ref "U1") (pin "19") (pinfunction "PB1/ADC_IN9/TIM3_CH4_19") (pintype "passive"))
    )
    (net (code "52") (name "unconnected-(U1-PB2{slash}BOOT1-Pad20)") (class "Default")
      (node (ref "U1") (pin "20") (pinfunction "PB2/BOOT1_20") (pintype "passive"))
    )
    (net (code "53") (name "unconnected-(U1-PB4{slash}JNTRST-Pad40)") (class "Default")
      (node (ref "U1") (pin "40") (pinfunction "PB4/JNTRST_40") (pintype "passive"))
    )
    (net (code "54") (name "unconnected-(U1-PB6{slash}I2C1_SCL{slash}TIM4_CH1-Pad42)") (class "Default")
      (node (ref "U1") (pin "42") (pinfunction "PB6/I2C1_SCL/TIM4_CH1_42") (pintype "passive"))
    )
    (net (code "55") (name "unconnected-(U1-PB7{slash}I2C1_SDA{slash}TIM4_CH2-Pad43)") (class "Default")
      (node (ref "U1") (pin "43") (pinfunction "PB7/I2C1_SDA/TIM4_CH2_43") (pintype "passive"))
    )
    (net (code "56") (name "unconnected-(U1-PB8{slash}TIM4_CH3-Pad45)") (class "Default")
      (node (ref "U1") (pin "45") (pinfunction "PB8/TIM4_CH3_45") (pintype "passive"))
    )
    (net (code "57") (name "unconnected-(U1-PB9{slash}TIM4_CH4-Pad46)") (class "Default")
      (node (ref "U1") (pin "46") (pinfunction "PB9/TIM4_CH4_46") (pintype "passive"))
    )
    (net (code "58") (name "unconnected-(U1-PB10{slash}I2C2_SCL{slash}USART3_TX-Pad21)") (class "Default")
      (node (ref "U1") (pin "21") (pinfunction "PB10/I2C2_SCL/USART3_TX_21") (pintype "passive"))
    )
    (net (code "59") (name "unconnected-(U1-PB11{slash}I2C2_SDA{slash}USART3_RX-Pad22)") (class "Default")
      (node (ref "U1") (pin "22") (pinfunction "PB11/I2C2_SDA/USART3_RX_22") (pintype "passive"))
    )
    (net (code "60") (name "unconnected-(U1-PB15{slash}SPI2_MOSI{slash}TIM1_CH3N-Pad28)") (class "Default")
      (node (ref "U1") (pin "28") (pinfunction "PB15/SPI2_MOSI/TIM1_CH3N_28") (pintype "passive"))
    )
    (net (code "61") (name "unconnected-(U1-PC13-ANTI_TAMP-Pad2)") (class "Default")
      (node (ref "U1") (pin "2") (pinfunction "PC13-ANTI_TAMP_2") (pintype "passive"))
    )
    (net (code "62") (name "unconnected-(U1-PC14-OSC32_IN-Pad3)") (class "Default")
      (node (ref "U1") (pin "3") (pinfunction "PC14-OSC32_IN_3") (pintype "passive"))
    )
    (net (code "63") (name "unconnected-(U1-PC15-OSC32_OUT-Pad4)") (class "Default")
      (node (ref "U1") (pin "4") (pinfunction "PC15-OSC32_OUT_4") (pintype "passive"))
    )
  )
)
